# SCH_SrProj_v1_5.net
KiCad netlist of a schematic drawn in EasyEDA
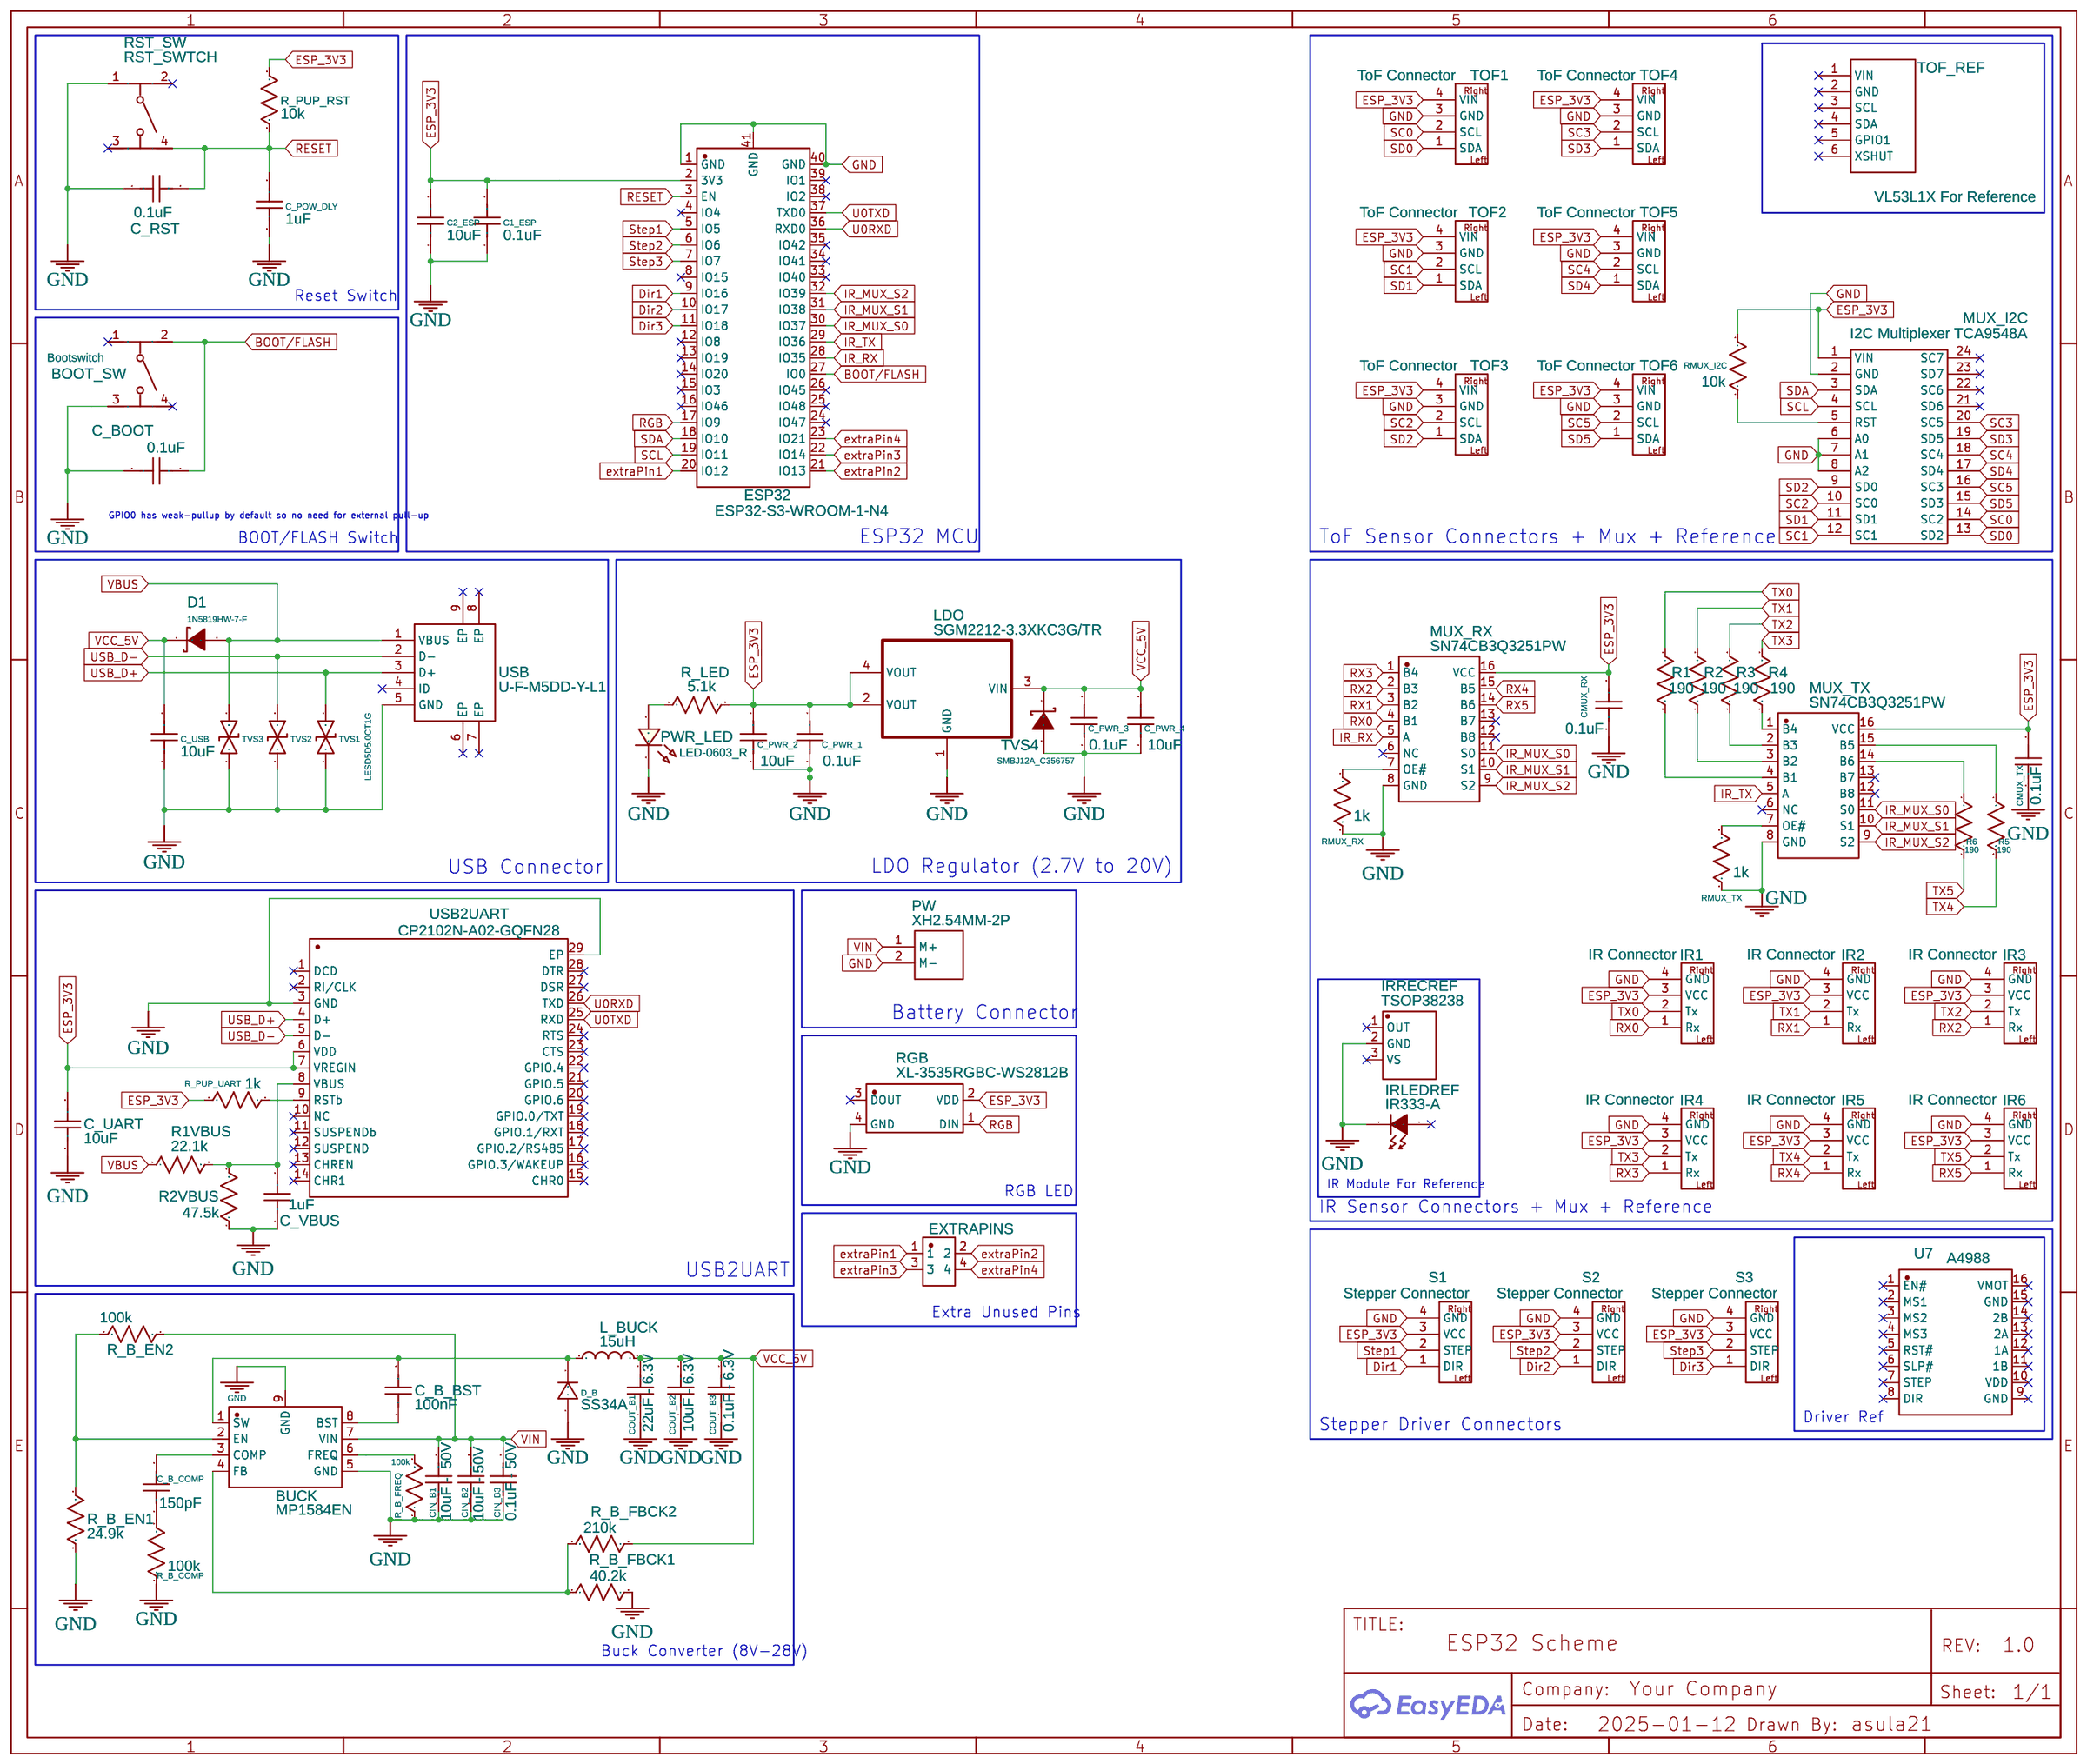
[diagram p0: schematic sheet]

(export (version "E")
  (design (tool "Eeschema 10.0.6"))
  (components
    (comp (ref "BOOT_SW")
      (value "Bootswitch")
      (fields
        (field (name "Manufacturer Part") "Switch,6*6*6Plastic head,260G, 0.25mm,Straight line")
        (field (name "Manufacturer") "BBJ")
      )
      (libsource (lib "") (part "Button-6x6x6mm_1"))
    )
    (comp (ref "BUCK") (value "MP1584EN") (libsource (lib "") (part "MP1584EN")))
    (comp (ref "C1_ESP") (value "0.1uF") (libsource (lib "") (part "C_0603_US_11")))
    (comp (ref "C2_ESP") (value "10uF") (libsource (lib "") (part "C_0603_US_8")))
    (comp (ref "CIN_B1") (value "10uF -  50V") (libsource (lib "") (part "C_0603_US_5")))
    (comp (ref "CIN_B2") (value "10uF - 50V") (libsource (lib "") (part "C_0603_US_5")))
    (comp (ref "CIN_B3") (value "0.1uF - 50V") (libsource (lib "") (part "C_0603_US_5")))
    (comp (ref "CMUX_RX") (value "0.1uF") (libsource (lib "") (part "C_0603_US_14")))
    (comp (ref "CMUX_TX") (value "0.1uF") (libsource (lib "") (part "C_0603_US_9")))
    (comp (ref "COUT_B1") (value "22uF - 6.3V") (libsource (lib "") (part "C_0603_US")))
    (comp (ref "COUT_B2") (value "10uF - 6.3V") (libsource (lib "") (part "C_0603_US")))
    (comp (ref "COUT_B3") (value "0.1uF - 6.3V") (libsource (lib "") (part "C_0603_US")))
    (comp (ref "C_BOOT") (value "0.1uF") (libsource (lib "") (part "C_0603_US_6")))
    (comp (ref "C_B_BST") (value "100nF") (libsource (lib "") (part "C_0603_US_4")))
    (comp (ref "C_B_COMP") (value "150pF") (libsource (lib "") (part "C_0603_US_13")))
    (comp (ref "C_POW_DLY") (value "1uF") (libsource (lib "") (part "C_0603_US_2")))
    (comp (ref "C_PWR_1") (value "0.1uF") (libsource (lib "") (part "C_0603_US_3")))
    (comp (ref "C_PWR_2") (value "10uF") (libsource (lib "") (part "C_0603_US_3")))
    (comp (ref "C_PWR_3") (value "0.1uF") (libsource (lib "") (part "C_0603_US_3")))
    (comp (ref "C_PWR_4") (value "10uF") (libsource (lib "") (part "C_0603_US_3")))
    (comp (ref "C_RST") (value "0.1uF") (libsource (lib "") (part "C_0603_US_12")))
    (comp (ref "C_UART") (value "10uF") (libsource (lib "") (part "C_0603_US_10")))
    (comp (ref "C_USB") (value "10uF") (libsource (lib "") (part "C_0603_US_1")))
    (comp (ref "C_VBUS") (value "1uF") (libsource (lib "") (part "C_0603_US_7")))
    (comp (ref "D1")
      (value "1N5819HW-7-F")
      (fields (field (name "Manufacturer") "DIODES(美台)"))
      (libsource (lib "") (part "1N5819HW-7-F"))
    )
    (comp (ref "D_B")
      (value "SS34A")
      (fields (field (name "Manufacturer") "YANGJIE(扬杰)"))
      (libsource (lib "") (part "SS34A"))
    )
    (comp (ref "ESP32")
      (value "ESP32-S3-WROOM-1-N4")
      (fields (field (name "Manufacturer") "ESPRESSIF(乐鑫)"))
      (libsource (lib "") (part "ESP32-S3-WROOM-1-N4"))
    )
    (comp (ref "EXTRAPINS")
      (value "排母/2.54MM2X2直排母袋装环保")
      (fields
        (field (name "Manufacturer Part") "排母/2.54mm2x2直排母袋装环保")
        (field (name "Manufacturer") "BOOMELE(博穆精密)")
      )
      (libsource (lib "") (part "排母/2.54MM2X2直排母袋装环保"))
    )
    (comp (ref "IR1") (value "IR Connector") (libsource (lib "") (part "MY XH2.54MM.4P_2")))
    (comp (ref "IR2") (value "IR Connector") (libsource (lib "") (part "MY XH2.54MM.4P_2")))
    (comp (ref "IR3") (value "IR Connector") (libsource (lib "") (part "MY XH2.54MM.4P_2")))
    (comp (ref "IR4") (value "IR Connector") (libsource (lib "") (part "MY XH2.54MM.4P_2")))
    (comp (ref "IR5") (value "IR Connector") (libsource (lib "") (part "MY XH2.54MM.4P_2")))
    (comp (ref "IR6") (value "IR Connector") (libsource (lib "") (part "MY XH2.54MM.4P_2")))
    (comp (ref "IRLEDREF")
      (value "IR333-A")
      (fields (field (name "Manufacturer") "EVERLIGHT(亿光)"))
      (libsource (lib "") (part "IR333-A"))
    )
    (comp (ref "IRRECREF")
      (value "TSOP38238")
      (fields (field (name "Manufacturer") "VISHAY(威世)"))
      (libsource (lib "") (part "TSOP38238"))
    )
    (comp (ref "LDO") (value "SGM2212-3.3XKC3G/TR") (libsource (lib "") (part "SGM2212-3.3XKC3G/TR")))
    (comp (ref "L_BUCK")
      (value "15uH")
      (fields (field (name "Manufacturer Part") "CYH127-4.7UH") (field (name "Manufacturer") "SHOU HAN(首韩)"))
      (libsource (lib "") (part "CYH127-4.7UH"))
    )
    (comp (ref "MUX_I2C")
      (value "I2C Multiplexer TCA9548A")
      (fields (field (name "Manufacturer Part") "IDSN-TCA9548A") (field (name "Manufacturer") "IDSN"))
      (libsource (lib "") (part "TCA9548A I2C MULTIPLEXER 8 CHANEL"))
    )
    (comp (ref "MUX_RX")
      (value "SN74CB3Q3251PW")
      (fields (field (name "Manufacturer") "TI(德州仪器)"))
      (libsource (lib "") (part "SN74CB3Q3251PW"))
    )
    (comp (ref "MUX_TX")
      (value "SN74CB3Q3251PW")
      (fields (field (name "Manufacturer") "TI(德州仪器)"))
      (libsource (lib "") (part "SN74CB3Q3251PW_1"))
    )
    (comp (ref "PW")
      (value "XH2.54MM-2P")
      (fields (field (name "Manufacturer Part") "Header P2 PH2.0 TUANLE"))
      (libsource (lib "") (part "PH2.0-2P"))
    )
    (comp (ref "PWR_LED")
      (value "LED-0603_R")
      (fields
        (field (name "Manufacturer Part") "19-217/R6C-AL1M2VY/3T")
        (field (name "Manufacturer") "EVERLIGHT(台湾亿光)")
      )
      (libsource (lib "") (part "LED-0603_R"))
    )
    (comp (ref "R1") (value "190") (libsource (lib "") (part "R_0805_US_1")))
    (comp (ref "R1VBUS") (value "22.1k") (libsource (lib "") (part "R_0603_US_3")))
    (comp (ref "R2") (value "190") (libsource (lib "") (part "R_0805_US")))
    (comp (ref "R2VBUS") (value "47.5k") (libsource (lib "") (part "R_0603_US_1")))
    (comp (ref "R3") (value "190") (libsource (lib "") (part "R_0805_US")))
    (comp (ref "R4") (value "190") (libsource (lib "") (part "R_0805_US")))
    (comp (ref "R5") (value "190") (libsource (lib "") (part "R_0805_US_1")))
    (comp (ref "R6") (value "190") (libsource (lib "") (part "R_0805_US")))
    (comp (ref "RGB")
      (value "XL-3535RGBC-WS2812B")
      (fields (field (name "Manufacturer") "XINGLIGHT(成兴光)"))
      (libsource (lib "") (part "XL-3535RGBC-WS2812B"))
    )
    (comp (ref "RMUX_I2C") (value "10k") (libsource (lib "") (part "R_0603_US_4")))
    (comp (ref "RMUX_RX") (value "1k") (libsource (lib "") (part "R_0603_US_11")))
    (comp (ref "RMUX_TX") (value "1k") (libsource (lib "") (part "R_0603_US_13")))
    (comp (ref "RST_SW")
      (value "RST_SWTCH")
      (fields
        (field (name "Manufacturer Part") "Switch,6*6*6Plastic head,260G, 0.25mm,Straight line")
        (field (name "Manufacturer") "BBJ")
      )
      (libsource (lib "") (part "Button-6x6x6mm"))
    )
    (comp (ref "R_B_COMP") (value "100k") (libsource (lib "") (part "R_0603_US_6")))
    (comp (ref "R_B_EN1") (value "24.9k") (libsource (lib "") (part "R_0603_US")))
    (comp (ref "R_B_EN2") (value "100k") (libsource (lib "") (part "R_0603_US_7")))
    (comp (ref "R_B_FBCK1") (value "40.2k") (libsource (lib "") (part "R_0603_US_10")))
    (comp (ref "R_B_FBCK2") (value "210k") (libsource (lib "") (part "R_0603_US_12")))
    (comp (ref "R_B_FREQ") (value "100k") (libsource (lib "") (part "R_0603_US_9")))
    (comp (ref "R_LED") (value "5.1k") (libsource (lib "") (part "R_0603_US_5")))
    (comp (ref "R_PUP_RST") (value "10k") (libsource (lib "") (part "R_0603_US_2")))
    (comp (ref "R_PUP_UART") (value "1k") (libsource (lib "") (part "R_0603_US_8")))
    (comp (ref "S1") (value "Stepper Connector") (libsource (lib "") (part "MY XH2.54MM.4P")))
    (comp (ref "S2") (value "Stepper Connector") (libsource (lib "") (part "MY XH2.54MM.4P")))
    (comp (ref "S3") (value "Stepper Connector") (libsource (lib "") (part "MY XH2.54MM.4P")))
    (comp (ref "TOF1") (value "ToF Connector") (libsource (lib "") (part "MY XH2.54MM.4P_1")))
    (comp (ref "TOF2") (value "ToF Connector") (libsource (lib "") (part "MY XH2.54MM.4P_1")))
    (comp (ref "TOF3") (value "ToF Connector") (libsource (lib "") (part "MY XH2.54MM.4P_1")))
    (comp (ref "TOF4") (value "ToF Connector") (libsource (lib "") (part "MY XH2.54MM.4P_1")))
    (comp (ref "TOF5") (value "ToF Connector") (libsource (lib "") (part "MY XH2.54MM.4P_1")))
    (comp (ref "TOF6") (value "ToF Connector") (libsource (lib "") (part "MY XH2.54MM.4P_1")))
    (comp (ref "TOF_REF")
      (value "VL53L1X For Reference")
      (fields (field (name "Manufacturer Part") "VL53L0X Time-of-Flight Distance Sensor VL53L0X"))
      (libsource (lib "") (part "VL53L1X_BREAKOUT"))
    )
    (comp (ref "TVS1")
      (value "LESD5D5.0CT1G")
      (fields (field (name "Manufacturer") "LRC(乐山无线电)"))
      (libsource (lib "") (part "LESD5D5.0CT1G"))
    )
    (comp (ref "TVS2")
      (value "LESD5D5.0CT1G")
      (fields (field (name "Manufacturer") "LRC(乐山无线电)"))
      (libsource (lib "") (part "LESD5D5.0CT1G"))
    )
    (comp (ref "TVS3")
      (value "LESD5D5.0CT1G")
      (fields (field (name "Manufacturer") "LRC(乐山无线电)"))
      (libsource (lib "") (part "LESD5D5.0CT1G"))
    )
    (comp (ref "TVS4")
      (value "SMBJ12A_C356757")
      (fields (field (name "Manufacturer Part") "SMBJ12A") (field (name "Manufacturer") "JJW(捷捷微)"))
      (libsource (lib "") (part "SMBJ12A_C356757"))
    )
    (comp (ref "U7") (value "A4988") (libsource (lib "") (part "A4988")))
    (comp (ref "USB")
      (value "U-F-M5DD-Y-L1")
      (fields (field (name "Manufacturer") "韩国韩荣"))
      (libsource (lib "") (part "U-F-M5DD-Y-L1"))
    )
    (comp (ref "USB2UART")
      (value "CP2102N-A02-GQFN28")
      (fields (field (name "Manufacturer") "SKYWORKS/SILICON LABS(芯科)"))
      (libsource (lib "") (part "CP2102N-A02-GQFN28"))
    )
  )
  (nets
    (net (code "1") (name "BOOT{slash}FLASH") (class "Default")
      (node (ref "BOOT_SW") (pin "2") (pinfunction "2_2") (pintype "unspecified"))
      (node (ref "C_BOOT") (pin "2") (pinfunction "2_2") (pintype "unspecified"))
      (node (ref "ESP32") (pin "27") (pinfunction "IO0_27") (pintype "unspecified"))
    )
    (net (code "2") (name "Dir1") (class "Default")
      (node (ref "ESP32") (pin "9") (pinfunction "IO16_9") (pintype "unspecified"))
      (node (ref "S1") (pin "1") (pinfunction "DIR_1") (pintype "unspecified"))
    )
    (net (code "3") (name "Dir2") (class "Default")
      (node (ref "ESP32") (pin "10") (pinfunction "IO17_10") (pintype "unspecified"))
      (node (ref "S2") (pin "1") (pinfunction "DIR_1") (pintype "unspecified"))
    )
    (net (code "4") (name "Dir3") (class "Default")
      (node (ref "ESP32") (pin "11") (pinfunction "IO18_11") (pintype "unspecified"))
      (node (ref "S3") (pin "1") (pinfunction "DIR_1") (pintype "unspecified"))
    )
    (net (code "5") (name "ESP_3V3") (class "Default")
      (node (ref "C1_ESP") (pin "2") (pinfunction "2_2") (pintype "unspecified"))
      (node (ref "C2_ESP") (pin "2") (pinfunction "2_2") (pintype "unspecified"))
      (node (ref "CMUX_RX") (pin "2") (pinfunction "2_2") (pintype "unspecified"))
      (node (ref "CMUX_TX") (pin "2") (pinfunction "2_2") (pintype "unspecified"))
      (node (ref "C_PWR_1") (pin "2") (pinfunction "2_2") (pintype "unspecified"))
      (node (ref "C_PWR_2") (pin "2") (pinfunction "2_2") (pintype "unspecified"))
      (node (ref "C_UART") (pin "2") (pinfunction "2_2") (pintype "unspecified"))
      (node (ref "ESP32") (pin "2") (pinfunction "3V3_2") (pintype "unspecified"))
      (node (ref "IR1") (pin "3") (pinfunction "VCC_3") (pintype "unspecified"))
      (node (ref "IR2") (pin "3") (pinfunction "VCC_3") (pintype "unspecified"))
      (node (ref "IR3") (pin "3") (pinfunction "VCC_3") (pintype "unspecified"))
      (node (ref "IR4") (pin "3") (pinfunction "VCC_3") (pintype "unspecified"))
      (node (ref "IR5") (pin "3") (pinfunction "VCC_3") (pintype "unspecified"))
      (node (ref "IR6") (pin "3") (pinfunction "VCC_3") (pintype "unspecified"))
      (node (ref "LDO") (pin "2") (pinfunction "VOUT_2") (pintype "unspecified"))
      (node (ref "LDO") (pin "4") (pinfunction "VOUT_4") (pintype "unspecified"))
      (node (ref "MUX_I2C") (pin "1") (pinfunction "VIN_1") (pintype "unspecified"))
      (node (ref "MUX_RX") (pin "16") (pinfunction "VCC_16") (pintype "unspecified"))
      (node (ref "MUX_TX") (pin "16") (pinfunction "VCC_16") (pintype "unspecified"))
      (node (ref "RGB") (pin "2") (pinfunction "VDD_2") (pintype "unspecified"))
      (node (ref "RMUX_I2C") (pin "2") (pinfunction "2_2") (pintype "unspecified"))
      (node (ref "R_LED") (pin "2") (pinfunction "2_2") (pintype "unspecified"))
      (node (ref "R_PUP_RST") (pin "2") (pinfunction "2_2") (pintype "unspecified"))
      (node (ref "R_PUP_UART") (pin "2") (pinfunction "2_2") (pintype "unspecified"))
      (node (ref "S1") (pin "3") (pinfunction "VCC_3") (pintype "unspecified"))
      (node (ref "S2") (pin "3") (pinfunction "VCC_3") (pintype "unspecified"))
      (node (ref "S3") (pin "3") (pinfunction "VCC_3") (pintype "unspecified"))
      (node (ref "TOF1") (pin "4") (pinfunction "VIN_4") (pintype "unspecified"))
      (node (ref "TOF2") (pin "4") (pinfunction "VIN_4") (pintype "unspecified"))
      (node (ref "TOF3") (pin "4") (pinfunction "VIN_4") (pintype "unspecified"))
      (node (ref "TOF4") (pin "4") (pinfunction "VIN_4") (pintype "unspecified"))
      (node (ref "TOF5") (pin "4") (pinfunction "VIN_4") (pintype "unspecified"))
      (node (ref "TOF6") (pin "4") (pinfunction "VIN_4") (pintype "unspecified"))
      (node (ref "USB2UART") (pin "6") (pinfunction "VDD_6") (pintype "unspecified"))
      (node (ref "USB2UART") (pin "7") (pinfunction "VREGIN_7") (pintype "unspecified"))
    )
    (net (code "6") (name "GND") (class "Default")
      (node (ref "BOOT_SW") (pin "3") (pinfunction "3_3") (pintype "unspecified"))
      (node (ref "BUCK") (pin "5") (pinfunction "GND_5") (pintype "unspecified"))
      (node (ref "BUCK") (pin "9") (pinfunction "GND_9") (pintype "unspecified"))
      (node (ref "C1_ESP") (pin "1") (pinfunction "1_1") (pintype "unspecified"))
      (node (ref "C2_ESP") (pin "1") (pinfunction "1_1") (pintype "unspecified"))
      (node (ref "CIN_B1") (pin "1") (pinfunction "1_1") (pintype "unspecified"))
      (node (ref "CIN_B2") (pin "1") (pinfunction "1_1") (pintype "unspecified"))
      (node (ref "CIN_B3") (pin "1") (pinfunction "1_1") (pintype "unspecified"))
      (node (ref "CMUX_RX") (pin "1") (pinfunction "1_1") (pintype "unspecified"))
      (node (ref "CMUX_TX") (pin "1") (pinfunction "1_1") (pintype "unspecified"))
      (node (ref "COUT_B1") (pin "1") (pinfunction "1_1") (pintype "unspecified"))
      (node (ref "COUT_B2") (pin "1") (pinfunction "1_1") (pintype "unspecified"))
      (node (ref "COUT_B3") (pin "1") (pinfunction "1_1") (pintype "unspecified"))
      (node (ref "C_BOOT") (pin "1") (pinfunction "1_1") (pintype "unspecified"))
      (node (ref "C_POW_DLY") (pin "1") (pinfunction "1_1") (pintype "unspecified"))
      (node (ref "C_PWR_1") (pin "1") (pinfunction "1_1") (pintype "unspecified"))
      (node (ref "C_PWR_2") (pin "1") (pinfunction "1_1") (pintype "unspecified"))
      (node (ref "C_PWR_3") (pin "1") (pinfunction "1_1") (pintype "unspecified"))
      (node (ref "C_PWR_4") (pin "1") (pinfunction "1_1") (pintype "unspecified"))
      (node (ref "C_RST") (pin "1") (pinfunction "1_1") (pintype "unspecified"))
      (node (ref "C_UART") (pin "1") (pinfunction "1_1") (pintype "unspecified"))
      (node (ref "C_USB") (pin "1") (pinfunction "1_1") (pintype "unspecified"))
      (node (ref "C_VBUS") (pin "2") (pinfunction "2_2") (pintype "unspecified"))
      (node (ref "D_B") (pin "2") (pinfunction "A_2") (pintype "unspecified"))
      (node (ref "ESP32") (pin "1") (pinfunction "GND_1") (pintype "unspecified"))
      (node (ref "ESP32") (pin "40") (pinfunction "GND_40") (pintype "unspecified"))
      (node (ref "ESP32") (pin "41") (pinfunction "GND_41") (pintype "unspecified"))
      (node (ref "IR1") (pin "4") (pinfunction "GND_4") (pintype "unspecified"))
      (node (ref "IR2") (pin "4") (pinfunction "GND_4") (pintype "unspecified"))
      (node (ref "IR3") (pin "4") (pinfunction "GND_4") (pintype "unspecified"))
      (node (ref "IR4") (pin "4") (pinfunction "GND_4") (pintype "unspecified"))
      (node (ref "IR5") (pin "4") (pinfunction "GND_4") (pintype "unspecified"))
      (node (ref "IR6") (pin "4") (pinfunction "GND_4") (pintype "unspecified"))
      (node (ref "IRLEDREF") (pin "2") (pinfunction "C_2") (pintype "input"))
      (node (ref "IRRECREF") (pin "2") (pinfunction "GND_2") (pintype "unspecified"))
      (node (ref "LDO") (pin "1") (pinfunction "GND_1") (pintype "unspecified"))
      (node (ref "MUX_I2C") (pin "2") (pinfunction "GND_2") (pintype "unspecified"))
      (node (ref "MUX_I2C") (pin "6") (pinfunction "A0_6") (pintype "unspecified"))
      (node (ref "MUX_I2C") (pin "7") (pinfunction "A1_7") (pintype "unspecified"))
      (node (ref "MUX_I2C") (pin "8") (pinfunction "A2_8") (pintype "unspecified"))
      (node (ref "MUX_RX") (pin "8") (pinfunction "GND_8") (pintype "unspecified"))
      (node (ref "MUX_TX") (pin "8") (pinfunction "GND_8") (pintype "unspecified"))
      (node (ref "PW") (pin "2") (pinfunction "M-_2") (pintype "unspecified"))
      (node (ref "PWR_LED") (pin "2") (pinfunction "2_2") (pintype "unspecified"))
      (node (ref "R2VBUS") (pin "1") (pinfunction "1_1") (pintype "unspecified"))
      (node (ref "RGB") (pin "4") (pinfunction "GND_4") (pintype "unspecified"))
      (node (ref "RMUX_RX") (pin "1") (pinfunction "1_1") (pintype "unspecified"))
      (node (ref "RMUX_TX") (pin "1") (pinfunction "1_1") (pintype "unspecified"))
      (node (ref "RST_SW") (pin "1") (pinfunction "1_1") (pintype "unspecified"))
      (node (ref "R_B_COMP") (pin "1") (pinfunction "1_1") (pintype "unspecified"))
      (node (ref "R_B_EN1") (pin "1") (pinfunction "1_1") (pintype "unspecified"))
      (node (ref "R_B_FBCK1") (pin "2") (pinfunction "2_2") (pintype "unspecified"))
      (node (ref "R_B_FREQ") (pin "1") (pinfunction "1_1") (pintype "unspecified"))
      (node (ref "S1") (pin "4") (pinfunction "GND_4") (pintype "unspecified"))
      (node (ref "S2") (pin "4") (pinfunction "GND_4") (pintype "unspecified"))
      (node (ref "S3") (pin "4") (pinfunction "GND_4") (pintype "unspecified"))
      (node (ref "TOF1") (pin "3") (pinfunction "GND_3") (pintype "unspecified"))
      (node (ref "TOF2") (pin "3") (pinfunction "GND_3") (pintype "unspecified"))
      (node (ref "TOF3") (pin "3") (pinfunction "GND_3") (pintype "unspecified"))
      (node (ref "TOF4") (pin "3") (pinfunction "GND_3") (pintype "unspecified"))
      (node (ref "TOF5") (pin "3") (pinfunction "GND_3") (pintype "unspecified"))
      (node (ref "TOF6") (pin "3") (pinfunction "GND_3") (pintype "unspecified"))
      (node (ref "TVS1") (pin "1") (pinfunction "1_1") (pintype "unspecified"))
      (node (ref "TVS2") (pin "1") (pinfunction "1_1") (pintype "unspecified"))
      (node (ref "TVS3") (pin "1") (pinfunction "1_1") (pintype "unspecified"))
      (node (ref "TVS4") (pin "2") (pinfunction "A_2") (pintype "unspecified"))
      (node (ref "USB") (pin "5") (pinfunction "GND_5") (pintype "unspecified"))
      (node (ref "USB2UART") (pin "29") (pinfunction "EP_29") (pintype "unspecified"))
      (node (ref "USB2UART") (pin "3") (pinfunction "GND_3") (pintype "unspecified"))
    )
    (net (code "7") (name "IR_MUX_S0") (class "Default")
      (node (ref "ESP32") (pin "30") (pinfunction "IO37_30") (pintype "unspecified"))
      (node (ref "MUX_RX") (pin "11") (pinfunction "S0_11") (pintype "unspecified"))
      (node (ref "MUX_TX") (pin "11") (pinfunction "S0_11") (pintype "unspecified"))
    )
    (net (code "8") (name "IR_MUX_S1") (class "Default")
      (node (ref "ESP32") (pin "31") (pinfunction "IO38_31") (pintype "unspecified"))
      (node (ref "MUX_RX") (pin "10") (pinfunction "S1_10") (pintype "unspecified"))
      (node (ref "MUX_TX") (pin "10") (pinfunction "S1_10") (pintype "unspecified"))
    )
    (net (code "9") (name "IR_MUX_S2") (class "Default")
      (node (ref "ESP32") (pin "32") (pinfunction "IO39_32") (pintype "unspecified"))
      (node (ref "MUX_RX") (pin "9") (pinfunction "S2_9") (pintype "unspecified"))
      (node (ref "MUX_TX") (pin "9") (pinfunction "S2_9") (pintype "unspecified"))
    )
    (net (code "10") (name "IR_RX") (class "Default")
      (node (ref "ESP32") (pin "28") (pinfunction "IO35_28") (pintype "unspecified"))
      (node (ref "MUX_RX") (pin "5") (pinfunction "A_5") (pintype "unspecified"))
    )
    (net (code "11") (name "IR_TX") (class "Default")
      (node (ref "ESP32") (pin "29") (pinfunction "IO36_29") (pintype "unspecified"))
      (node (ref "MUX_TX") (pin "5") (pinfunction "A_5") (pintype "unspecified"))
    )
    (net (code "12") (name "Net-(BUCK-BST)") (class "Default")
      (node (ref "BUCK") (pin "8") (pinfunction "BST_8") (pintype "unspecified"))
      (node (ref "C_B_BST") (pin "1") (pinfunction "1_1") (pintype "unspecified"))
    )
    (net (code "13") (name "Net-(BUCK-COMP)") (class "Default")
      (node (ref "BUCK") (pin "3") (pinfunction "COMP_3") (pintype "unspecified"))
      (node (ref "C_B_COMP") (pin "2") (pinfunction "2_2") (pintype "unspecified"))
    )
    (net (code "14") (name "Net-(BUCK-EN)") (class "Default")
      (node (ref "BUCK") (pin "2") (pinfunction "EN_2") (pintype "unspecified"))
      (node (ref "R_B_EN1") (pin "2") (pinfunction "2_2") (pintype "unspecified"))
      (node (ref "R_B_EN2") (pin "1") (pinfunction "1_1") (pintype "unspecified"))
    )
    (net (code "15") (name "Net-(BUCK-FB)") (class "Default")
      (node (ref "BUCK") (pin "4") (pinfunction "FB_4") (pintype "unspecified"))
      (node (ref "R_B_FBCK1") (pin "1") (pinfunction "1_1") (pintype "unspecified"))
      (node (ref "R_B_FBCK2") (pin "2") (pinfunction "2_2") (pintype "unspecified"))
    )
    (net (code "16") (name "Net-(BUCK-FREQ)") (class "Default")
      (node (ref "BUCK") (pin "6") (pinfunction "FREQ_6") (pintype "unspecified"))
      (node (ref "R_B_FREQ") (pin "2") (pinfunction "2_2") (pintype "unspecified"))
    )
    (net (code "17") (name "Net-(BUCK-SW)") (class "Default")
      (node (ref "BUCK") (pin "1") (pinfunction "SW_1") (pintype "unspecified"))
      (node (ref "C_B_BST") (pin "2") (pinfunction "2_2") (pintype "unspecified"))
      (node (ref "D_B") (pin "1") (pinfunction "C_1") (pintype "unspecified"))
      (node (ref "L_BUCK") (pin "1") (pinfunction "1_1") (pintype "unspecified"))
    )
    (net (code "18") (name "Net-(C_B_COMP-Pad1)") (class "Default")
      (node (ref "C_B_COMP") (pin "1") (pinfunction "1_1") (pintype "unspecified"))
      (node (ref "R_B_COMP") (pin "2") (pinfunction "2_2") (pintype "unspecified"))
    )
    (net (code "19") (name "Net-(MUX_I2C-RST)") (class "Default")
      (node (ref "MUX_I2C") (pin "5") (pinfunction "RST_5") (pintype "unspecified"))
      (node (ref "RMUX_I2C") (pin "1") (pinfunction "1_1") (pintype "unspecified"))
    )
    (net (code "20") (name "Net-(MUX_RX-OE#)") (class "Default")
      (node (ref "MUX_RX") (pin "7") (pinfunction "OE#_7") (pintype "unspecified"))
      (node (ref "RMUX_RX") (pin "2") (pinfunction "2_2") (pintype "unspecified"))
    )
    (net (code "21") (name "Net-(MUX_TX-B1)") (class "Default")
      (node (ref "MUX_TX") (pin "4") (pinfunction "B1_4") (pintype "unspecified"))
      (node (ref "R1") (pin "2") (pinfunction "2_2") (pintype "unspecified"))
    )
    (net (code "22") (name "Net-(MUX_TX-B2)") (class "Default")
      (node (ref "MUX_TX") (pin "3") (pinfunction "B2_3") (pintype "unspecified"))
      (node (ref "R2") (pin "1") (pinfunction "1_1") (pintype "unspecified"))
    )
    (net (code "23") (name "Net-(MUX_TX-B3)") (class "Default")
      (node (ref "MUX_TX") (pin "2") (pinfunction "B3_2") (pintype "unspecified"))
      (node (ref "R3") (pin "1") (pinfunction "1_1") (pintype "unspecified"))
    )
    (net (code "24") (name "Net-(MUX_TX-B4)") (class "Default")
      (node (ref "MUX_TX") (pin "1") (pinfunction "B4_1") (pintype "unspecified"))
      (node (ref "R4") (pin "1") (pinfunction "1_1") (pintype "unspecified"))
    )
    (net (code "25") (name "Net-(MUX_TX-B5)") (class "Default")
      (node (ref "MUX_TX") (pin "15") (pinfunction "B5_15") (pintype "unspecified"))
      (node (ref "R5") (pin "1") (pinfunction "1_1") (pintype "unspecified"))
    )
    (net (code "26") (name "Net-(MUX_TX-B6)") (class "Default")
      (node (ref "MUX_TX") (pin "14") (pinfunction "B6_14") (pintype "unspecified"))
      (node (ref "R6") (pin "2") (pinfunction "2_2") (pintype "unspecified"))
    )
    (net (code "27") (name "Net-(MUX_TX-OE#)") (class "Default")
      (node (ref "MUX_TX") (pin "7") (pinfunction "OE#_7") (pintype "unspecified"))
      (node (ref "RMUX_TX") (pin "2") (pinfunction "2_2") (pintype "unspecified"))
    )
    (net (code "28") (name "Net-(PWR_LED-Pad1)") (class "Default")
      (node (ref "PWR_LED") (pin "1") (pinfunction "1_1") (pintype "unspecified"))
      (node (ref "R_LED") (pin "1") (pinfunction "1_1") (pintype "unspecified"))
    )
    (net (code "29") (name "Net-(USB2UART-RSTb)") (class "Default")
      (node (ref "R_PUP_UART") (pin "1") (pinfunction "1_1") (pintype "unspecified"))
      (node (ref "USB2UART") (pin "9") (pinfunction "RSTb_9") (pintype "unspecified"))
    )
    (net (code "30") (name "Net-(USB2UART-VBUS)") (class "Default")
      (node (ref "C_VBUS") (pin "1") (pinfunction "1_1") (pintype "unspecified"))
      (node (ref "R1VBUS") (pin "2") (pinfunction "2_2") (pintype "unspecified"))
      (node (ref "R2VBUS") (pin "2") (pinfunction "2_2") (pintype "unspecified"))
      (node (ref "USB2UART") (pin "8") (pinfunction "VBUS_8") (pintype "unspecified"))
    )
    (net (code "31") (name "RESET") (class "Default")
      (node (ref "C_POW_DLY") (pin "2") (pinfunction "2_2") (pintype "unspecified"))
      (node (ref "C_RST") (pin "2") (pinfunction "2_2") (pintype "unspecified"))
      (node (ref "ESP32") (pin "3") (pinfunction "EN_3") (pintype "unspecified"))
      (node (ref "RST_SW") (pin "4") (pinfunction "4_4") (pintype "unspecified"))
      (node (ref "R_PUP_RST") (pin "1") (pinfunction "1_1") (pintype "unspecified"))
    )
    (net (code "32") (name "RGB") (class "Default")
      (node (ref "ESP32") (pin "17") (pinfunction "IO9_17") (pintype "unspecified"))
      (node (ref "RGB") (pin "1") (pinfunction "DIN_1") (pintype "unspecified"))
    )
    (net (code "33") (name "RX0") (class "Default")
      (node (ref "IR1") (pin "1") (pinfunction "Rx_1") (pintype "unspecified"))
      (node (ref "MUX_RX") (pin "4") (pinfunction "B1_4") (pintype "unspecified"))
    )
    (net (code "34") (name "RX1") (class "Default")
      (node (ref "IR2") (pin "1") (pinfunction "Rx_1") (pintype "unspecified"))
      (node (ref "MUX_RX") (pin "3") (pinfunction "B2_3") (pintype "unspecified"))
    )
    (net (code "35") (name "RX2") (class "Default")
      (node (ref "IR3") (pin "1") (pinfunction "Rx_1") (pintype "unspecified"))
      (node (ref "MUX_RX") (pin "2") (pinfunction "B3_2") (pintype "unspecified"))
    )
    (net (code "36") (name "RX3") (class "Default")
      (node (ref "IR4") (pin "1") (pinfunction "Rx_1") (pintype "unspecified"))
      (node (ref "MUX_RX") (pin "1") (pinfunction "B4_1") (pintype "unspecified"))
    )
    (net (code "37") (name "RX4") (class "Default")
      (node (ref "IR5") (pin "1") (pinfunction "Rx_1") (pintype "unspecified"))
      (node (ref "MUX_RX") (pin "15") (pinfunction "B5_15") (pintype "unspecified"))
    )
    (net (code "38") (name "RX5") (class "Default")
      (node (ref "IR6") (pin "1") (pinfunction "Rx_1") (pintype "unspecified"))
      (node (ref "MUX_RX") (pin "14") (pinfunction "B6_14") (pintype "unspecified"))
    )
    (net (code "39") (name "SC0") (class "Default")
      (node (ref "MUX_I2C") (pin "14") (pinfunction "SC2_14") (pintype "unspecified"))
      (node (ref "TOF1") (pin "2") (pinfunction "SCL_2") (pintype "unspecified"))
    )
    (net (code "40") (name "SC1") (class "Default")
      (node (ref "MUX_I2C") (pin "12") (pinfunction "SC1_12") (pintype "unspecified"))
      (node (ref "TOF2") (pin "2") (pinfunction "SCL_2") (pintype "unspecified"))
    )
    (net (code "41") (name "SC2") (class "Default")
      (node (ref "MUX_I2C") (pin "10") (pinfunction "SC0_10") (pintype "unspecified"))
      (node (ref "TOF3") (pin "2") (pinfunction "SCL_2") (pintype "unspecified"))
    )
    (net (code "42") (name "SC3") (class "Default")
      (node (ref "MUX_I2C") (pin "20") (pinfunction "SC5_20") (pintype "unspecified"))
      (node (ref "TOF4") (pin "2") (pinfunction "SCL_2") (pintype "unspecified"))
    )
    (net (code "43") (name "SC4") (class "Default")
      (node (ref "MUX_I2C") (pin "18") (pinfunction "SC4_18") (pintype "unspecified"))
      (node (ref "TOF5") (pin "2") (pinfunction "SCL_2") (pintype "unspecified"))
    )
    (net (code "44") (name "SC5") (class "Default")
      (node (ref "MUX_I2C") (pin "16") (pinfunction "SC3_16") (pintype "unspecified"))
      (node (ref "TOF6") (pin "2") (pinfunction "SCL_2") (pintype "unspecified"))
    )
    (net (code "45") (name "SCL") (class "Default")
      (node (ref "ESP32") (pin "19") (pinfunction "IO11_19") (pintype "unspecified"))
      (node (ref "MUX_I2C") (pin "4") (pinfunction "SCL_4") (pintype "unspecified"))
    )
    (net (code "46") (name "SD0") (class "Default")
      (node (ref "MUX_I2C") (pin "13") (pinfunction "SD2_13") (pintype "unspecified"))
      (node (ref "TOF1") (pin "1") (pinfunction "SDA_1") (pintype "unspecified"))
    )
    (net (code "47") (name "SD1") (class "Default")
      (node (ref "MUX_I2C") (pin "11") (pinfunction "SD1_11") (pintype "unspecified"))
      (node (ref "TOF2") (pin "1") (pinfunction "SDA_1") (pintype "unspecified"))
    )
    (net (code "48") (name "SD2") (class "Default")
      (node (ref "MUX_I2C") (pin "9") (pinfunction "SD0_9") (pintype "unspecified"))
      (node (ref "TOF3") (pin "1") (pinfunction "SDA_1") (pintype "unspecified"))
    )
    (net (code "49") (name "SD3") (class "Default")
      (node (ref "MUX_I2C") (pin "19") (pinfunction "SD5_19") (pintype "unspecified"))
      (node (ref "TOF4") (pin "1") (pinfunction "SDA_1") (pintype "unspecified"))
    )
    (net (code "50") (name "SD4") (class "Default")
      (node (ref "MUX_I2C") (pin "17") (pinfunction "SD4_17") (pintype "unspecified"))
      (node (ref "TOF5") (pin "1") (pinfunction "SDA_1") (pintype "unspecified"))
    )
    (net (code "51") (name "SD5") (class "Default")
      (node (ref "MUX_I2C") (pin "15") (pinfunction "SD3_15") (pintype "unspecified"))
      (node (ref "TOF6") (pin "1") (pinfunction "SDA_1") (pintype "unspecified"))
    )
    (net (code "52") (name "SDA") (class "Default")
      (node (ref "ESP32") (pin "18") (pinfunction "IO10_18") (pintype "unspecified"))
      (node (ref "MUX_I2C") (pin "3") (pinfunction "SDA_3") (pintype "unspecified"))
    )
    (net (code "53") (name "Step1") (class "Default")
      (node (ref "ESP32") (pin "5") (pinfunction "IO5_5") (pintype "unspecified"))
      (node (ref "S1") (pin "2") (pinfunction "STEP_2") (pintype "unspecified"))
    )
    (net (code "54") (name "Step2") (class "Default")
      (node (ref "ESP32") (pin "6") (pinfunction "IO6_6") (pintype "unspecified"))
      (node (ref "S2") (pin "2") (pinfunction "STEP_2") (pintype "unspecified"))
    )
    (net (code "55") (name "Step3") (class "Default")
      (node (ref "ESP32") (pin "7") (pinfunction "IO7_7") (pintype "unspecified"))
      (node (ref "S3") (pin "2") (pinfunction "STEP_2") (pintype "unspecified"))
    )
    (net (code "56") (name "TX0") (class "Default")
      (node (ref "IR1") (pin "2") (pinfunction "Tx_2") (pintype "unspecified"))
      (node (ref "R1") (pin "1") (pinfunction "1_1") (pintype "unspecified"))
    )
    (net (code "57") (name "TX1") (class "Default")
      (node (ref "IR2") (pin "2") (pinfunction "Tx_2") (pintype "unspecified"))
      (node (ref "R2") (pin "2") (pinfunction "2_2") (pintype "unspecified"))
    )
    (net (code "58") (name "TX2") (class "Default")
      (node (ref "IR3") (pin "2") (pinfunction "Tx_2") (pintype "unspecified"))
      (node (ref "R3") (pin "2") (pinfunction "2_2") (pintype "unspecified"))
    )
    (net (code "59") (name "TX3") (class "Default")
      (node (ref "IR4") (pin "2") (pinfunction "Tx_2") (pintype "unspecified"))
      (node (ref "R4") (pin "2") (pinfunction "2_2") (pintype "unspecified"))
    )
    (net (code "60") (name "TX4") (class "Default")
      (node (ref "IR5") (pin "2") (pinfunction "Tx_2") (pintype "unspecified"))
      (node (ref "R5") (pin "2") (pinfunction "2_2") (pintype "unspecified"))
    )
    (net (code "61") (name "TX5") (class "Default")
      (node (ref "IR6") (pin "2") (pinfunction "Tx_2") (pintype "unspecified"))
      (node (ref "R6") (pin "1") (pinfunction "1_1") (pintype "unspecified"))
    )
    (net (code "62") (name "U0RXD") (class "Default")
      (node (ref "ESP32") (pin "36") (pinfunction "RXD0_36") (pintype "unspecified"))
      (node (ref "USB2UART") (pin "26") (pinfunction "TXD_26") (pintype "unspecified"))
    )
    (net (code "63") (name "U0TXD") (class "Default")
      (node (ref "ESP32") (pin "37") (pinfunction "TXD0_37") (pintype "unspecified"))
      (node (ref "USB2UART") (pin "25") (pinfunction "RXD_25") (pintype "unspecified"))
    )
    (net (code "64") (name "USB_D+") (class "Default")
      (node (ref "TVS1") (pin "2") (pinfunction "2_2") (pintype "unspecified"))
      (node (ref "USB") (pin "3") (pinfunction "D+_3") (pintype "unspecified"))
      (node (ref "USB2UART") (pin "4") (pinfunction "D+_4") (pintype "unspecified"))
    )
    (net (code "65") (name "USB_D-") (class "Default")
      (node (ref "TVS2") (pin "2") (pinfunction "2_2") (pintype "unspecified"))
      (node (ref "USB") (pin "2") (pinfunction "D-_2") (pintype "unspecified"))
      (node (ref "USB2UART") (pin "5") (pinfunction "D-_5") (pintype "unspecified"))
    )
    (net (code "66") (name "VBUS") (class "Default")
      (node (ref "D1") (pin "2") (pinfunction "A_2") (pintype "unspecified"))
      (node (ref "R1VBUS") (pin "1") (pinfunction "1_1") (pintype "unspecified"))
      (node (ref "TVS3") (pin "2") (pinfunction "2_2") (pintype "unspecified"))
      (node (ref "USB") (pin "1") (pinfunction "VBUS_1") (pintype "unspecified"))
    )
    (net (code "67") (name "VCC_5V") (class "Default")
      (node (ref "COUT_B1") (pin "2") (pinfunction "2_2") (pintype "unspecified"))
      (node (ref "COUT_B2") (pin "2") (pinfunction "2_2") (pintype "unspecified"))
      (node (ref "COUT_B3") (pin "2") (pinfunction "2_2") (pintype "unspecified"))
      (node (ref "C_PWR_3") (pin "2") (pinfunction "2_2") (pintype "unspecified"))
      (node (ref "C_PWR_4") (pin "2") (pinfunction "2_2") (pintype "unspecified"))
      (node (ref "C_USB") (pin "2") (pinfunction "2_2") (pintype "unspecified"))
      (node (ref "D1") (pin "1") (pinfunction "K_1") (pintype "unspecified"))
      (node (ref "LDO") (pin "3") (pinfunction "VIN_3") (pintype "unspecified"))
      (node (ref "L_BUCK") (pin "2") (pinfunction "2_2") (pintype "unspecified"))
      (node (ref "R_B_FBCK2") (pin "1") (pinfunction "1_1") (pintype "unspecified"))
      (node (ref "TVS4") (pin "1") (pinfunction "K_1") (pintype "unspecified"))
    )
    (net (code "68") (name "VIN") (class "Default")
      (node (ref "BUCK") (pin "7") (pinfunction "VIN_7") (pintype "unspecified"))
      (node (ref "CIN_B1") (pin "2") (pinfunction "2_2") (pintype "unspecified"))
      (node (ref "CIN_B2") (pin "2") (pinfunction "2_2") (pintype "unspecified"))
      (node (ref "CIN_B3") (pin "2") (pinfunction "2_2") (pintype "unspecified"))
      (node (ref "PW") (pin "1") (pinfunction "M+_1") (pintype "unspecified"))
      (node (ref "R_B_EN2") (pin "2") (pinfunction "2_2") (pintype "unspecified"))
    )
    (net (code "69") (name "extraPin1") (class "Default")
      (node (ref "ESP32") (pin "20") (pinfunction "IO12_20") (pintype "unspecified"))
      (node (ref "EXTRAPINS") (pin "1") (pinfunction "1_1") (pintype "unspecified"))
    )
    (net (code "70") (name "extraPin2") (class "Default")
      (node (ref "ESP32") (pin "21") (pinfunction "IO13_21") (pintype "unspecified"))
      (node (ref "EXTRAPINS") (pin "2") (pinfunction "2_2") (pintype "unspecified"))
    )
    (net (code "71") (name "extraPin3") (class "Default")
      (node (ref "ESP32") (pin "22") (pinfunction "IO14_22") (pintype "unspecified"))
      (node (ref "EXTRAPINS") (pin "3") (pinfunction "3_3") (pintype "unspecified"))
    )
    (net (code "72") (name "extraPin4") (class "Default")
      (node (ref "ESP32") (pin "23") (pinfunction "IO21_23") (pintype "unspecified"))
      (node (ref "EXTRAPINS") (pin "4") (pinfunction "4_4") (pintype "unspecified"))
    )
    (net (code "73") (name "unconnected-(BOOT_SW-Pad1)") (class "Default")
      (node (ref "BOOT_SW") (pin "1") (pinfunction "1_1") (pintype "unspecified+no_connect"))
    )
    (net (code "74") (name "unconnected-(BOOT_SW-Pad4)") (class "Default")
      (node (ref "BOOT_SW") (pin "4") (pinfunction "4_4") (pintype "unspecified+no_connect"))
    )
    (net (code "75") (name "unconnected-(ESP32-IO1-Pad39)") (class "Default")
      (node (ref "ESP32") (pin "39") (pinfunction "IO1_39") (pintype "unspecified+no_connect"))
    )
    (net (code "76") (name "unconnected-(ESP32-IO2-Pad38)") (class "Default")
      (node (ref "ESP32") (pin "38") (pinfunction "IO2_38") (pintype "unspecified+no_connect"))
    )
    (net (code "77") (name "unconnected-(ESP32-IO3-Pad15)") (class "Default")
      (node (ref "ESP32") (pin "15") (pinfunction "IO3_15") (pintype "unspecified+no_connect"))
    )
    (net (code "78") (name "unconnected-(ESP32-IO4-Pad4)") (class "Default")
      (node (ref "ESP32") (pin "4") (pinfunction "IO4_4") (pintype "unspecified+no_connect"))
    )
    (net (code "79") (name "unconnected-(ESP32-IO8-Pad12)") (class "Default")
      (node (ref "ESP32") (pin "12") (pinfunction "IO8_12") (pintype "unspecified+no_connect"))
    )
    (net (code "80") (name "unconnected-(ESP32-IO15-Pad8)") (class "Default")
      (node (ref "ESP32") (pin "8") (pinfunction "IO15_8") (pintype "unspecified+no_connect"))
    )
    (net (code "81") (name "unconnected-(ESP32-IO19-Pad13)") (class "Default")
      (node (ref "ESP32") (pin "13") (pinfunction "IO19_13") (pintype "unspecified+no_connect"))
    )
    (net (code "82") (name "unconnected-(ESP32-IO20-Pad14)") (class "Default")
      (node (ref "ESP32") (pin "14") (pinfunction "IO20_14") (pintype "unspecified+no_connect"))
    )
    (net (code "83") (name "unconnected-(ESP32-IO40-Pad33)") (class "Default")
      (node (ref "ESP32") (pin "33") (pinfunction "IO40_33") (pintype "unspecified+no_connect"))
    )
    (net (code "84") (name "unconnected-(ESP32-IO41-Pad34)") (class "Default")
      (node (ref "ESP32") (pin "34") (pinfunction "IO41_34") (pintype "unspecified+no_connect"))
    )
    (net (code "85") (name "unconnected-(ESP32-IO42-Pad35)") (class "Default")
      (node (ref "ESP32") (pin "35") (pinfunction "IO42_35") (pintype "unspecified+no_connect"))
    )
    (net (code "86") (name "unconnected-(ESP32-IO45-Pad26)") (class "Default")
      (node (ref "ESP32") (pin "26") (pinfunction "IO45_26") (pintype "unspecified+no_connect"))
    )
    (net (code "87") (name "unconnected-(ESP32-IO46-Pad16)") (class "Default")
      (node (ref "ESP32") (pin "16") (pinfunction "IO46_16") (pintype "unspecified+no_connect"))
    )
    (net (code "88") (name "unconnected-(ESP32-IO47-Pad24)") (class "Default")
      (node (ref "ESP32") (pin "24") (pinfunction "IO47_24") (pintype "unspecified+no_connect"))
    )
    (net (code "89") (name "unconnected-(ESP32-IO48-Pad25)") (class "Default")
      (node (ref "ESP32") (pin "25") (pinfunction "IO48_25") (pintype "unspecified+no_connect"))
    )
    (net (code "90") (name "unconnected-(IRLEDREF-A-Pad1)") (class "Default")
      (node (ref "IRLEDREF") (pin "1") (pinfunction "A_1") (pintype "input+no_connect"))
    )
    (net (code "91") (name "unconnected-(IRRECREF-OUT-Pad1)") (class "Default")
      (node (ref "IRRECREF") (pin "1") (pinfunction "OUT_1") (pintype "unspecified+no_connect"))
    )
    (net (code "92") (name "unconnected-(IRRECREF-VS-Pad3)") (class "Default")
      (node (ref "IRRECREF") (pin "3") (pinfunction "VS_3") (pintype "unspecified+no_connect"))
    )
    (net (code "93") (name "unconnected-(MUX_I2C-SC6-Pad22)") (class "Default")
      (node (ref "MUX_I2C") (pin "22") (pinfunction "SC6_22") (pintype "unspecified+no_connect"))
    )
    (net (code "94") (name "unconnected-(MUX_I2C-SC7-Pad24)") (class "Default")
      (node (ref "MUX_I2C") (pin "24") (pinfunction "SC7_24") (pintype "unspecified+no_connect"))
    )
    (net (code "95") (name "unconnected-(MUX_I2C-SD6-Pad21)") (class "Default")
      (node (ref "MUX_I2C") (pin "21") (pinfunction "SD6_21") (pintype "unspecified+no_connect"))
    )
    (net (code "96") (name "unconnected-(MUX_I2C-SD7-Pad23)") (class "Default")
      (node (ref "MUX_I2C") (pin "23") (pinfunction "SD7_23") (pintype "unspecified+no_connect"))
    )
    (net (code "97") (name "unconnected-(MUX_RX-B7-Pad13)") (class "Default")
      (node (ref "MUX_RX") (pin "13") (pinfunction "B7_13") (pintype "unspecified+no_connect"))
    )
    (net (code "98") (name "unconnected-(MUX_RX-B8-Pad12)") (class "Default")
      (node (ref "MUX_RX") (pin "12") (pinfunction "B8_12") (pintype "unspecified+no_connect"))
    )
    (net (code "99") (name "unconnected-(MUX_RX-NC-Pad6)") (class "Default")
      (node (ref "MUX_RX") (pin "6") (pinfunction "NC_6") (pintype "unspecified+no_connect"))
    )
    (net (code "100") (name "unconnected-(MUX_TX-B7-Pad13)") (class "Default")
      (node (ref "MUX_TX") (pin "13") (pinfunction "B7_13") (pintype "unspecified+no_connect"))
    )
    (net (code "101") (name "unconnected-(MUX_TX-B8-Pad12)") (class "Default")
      (node (ref "MUX_TX") (pin "12") (pinfunction "B8_12") (pintype "unspecified+no_connect"))
    )
    (net (code "102") (name "unconnected-(MUX_TX-NC-Pad6)") (class "Default")
      (node (ref "MUX_TX") (pin "6") (pinfunction "NC_6") (pintype "unspecified+no_connect"))
    )
    (net (code "103") (name "unconnected-(RGB-DOUT-Pad3)") (class "Default")
      (node (ref "RGB") (pin "3") (pinfunction "DOUT_3") (pintype "unspecified+no_connect"))
    )
    (net (code "104") (name "unconnected-(RST_SW-Pad2)") (class "Default")
      (node (ref "RST_SW") (pin "2") (pinfunction "2_2") (pintype "unspecified+no_connect"))
    )
    (net (code "105") (name "unconnected-(RST_SW-Pad3)") (class "Default")
      (node (ref "RST_SW") (pin "3") (pinfunction "3_3") (pintype "unspecified+no_connect"))
    )
    (net (code "106") (name "unconnected-(TOF_REF-GND-Pad2)") (class "Default")
      (node (ref "TOF_REF") (pin "2") (pinfunction "GND_2") (pintype "unspecified+no_connect"))
    )
    (net (code "107") (name "unconnected-(TOF_REF-GPIO1-Pad5)") (class "Default")
      (node (ref "TOF_REF") (pin "5") (pinfunction "GPIO1_5") (pintype "unspecified+no_connect"))
    )
    (net (code "108") (name "unconnected-(TOF_REF-SCL-Pad3)") (class "Default")
      (node (ref "TOF_REF") (pin "3") (pinfunction "SCL_3") (pintype "unspecified+no_connect"))
    )
    (net (code "109") (name "unconnected-(TOF_REF-SDA-Pad4)") (class "Default")
      (node (ref "TOF_REF") (pin "4") (pinfunction "SDA_4") (pintype "unspecified+no_connect"))
    )
    (net (code "110") (name "unconnected-(TOF_REF-VIN-Pad1)") (class "Default")
      (node (ref "TOF_REF") (pin "1") (pinfunction "VIN_1") (pintype "unspecified+no_connect"))
    )
    (net (code "111") (name "unconnected-(TOF_REF-XSHUT-Pad6)") (class "Default")
      (node (ref "TOF_REF") (pin "6") (pinfunction "XSHUT_6") (pintype "unspecified+no_connect"))
    )
    (net (code "112") (name "unconnected-(U7-1A-Pad12)") (class "Default")
      (node (ref "U7") (pin "12") (pinfunction "1A_12") (pintype "unspecified+no_connect"))
    )
    (net (code "113") (name "unconnected-(U7-1B-Pad11)") (class "Default")
      (node (ref "U7") (pin "11") (pinfunction "1B_11") (pintype "unspecified+no_connect"))
    )
    (net (code "114") (name "unconnected-(U7-2A-Pad13)") (class "Default")
      (node (ref "U7") (pin "13") (pinfunction "2A_13") (pintype "unspecified+no_connect"))
    )
    (net (code "115") (name "unconnected-(U7-2B-Pad14)") (class "Default")
      (node (ref "U7") (pin "14") (pinfunction "2B_14") (pintype "unspecified+no_connect"))
    )
    (net (code "116") (name "unconnected-(U7-DIR-Pad8)") (class "Default")
      (node (ref "U7") (pin "8") (pinfunction "DIR_8") (pintype "unspecified+no_connect"))
    )
    (net (code "117") (name "unconnected-(U7-EN#-Pad1)") (class "Default")
      (node (ref "U7") (pin "1") (pinfunction "EN#_1") (pintype "unspecified+no_connect"))
    )
    (net (code "118") (name "unconnected-(U7-GND-Pad9)") (class "Default")
      (node (ref "U7") (pin "9") (pinfunction "GND_9") (pintype "unspecified+no_connect"))
    )
    (net (code "119") (name "unconnected-(U7-GND-Pad15)") (class "Default")
      (node (ref "U7") (pin "15") (pinfunction "GND_15") (pintype "unspecified+no_connect"))
    )
    (net (code "120") (name "unconnected-(U7-MS1-Pad2)") (class "Default")
      (node (ref "U7") (pin "2") (pinfunction "MS1_2") (pintype "unspecified+no_connect"))
    )
    (net (code "121") (name "unconnected-(U7-MS2-Pad3)") (class "Default")
      (node (ref "U7") (pin "3") (pinfunction "MS2_3") (pintype "unspecified+no_connect"))
    )
    (net (code "122") (name "unconnected-(U7-MS3-Pad4)") (class "Default")
      (node (ref "U7") (pin "4") (pinfunction "MS3_4") (pintype "unspecified+no_connect"))
    )
    (net (code "123") (name "unconnected-(U7-RST#-Pad5)") (class "Default")
      (node (ref "U7") (pin "5") (pinfunction "RST#_5") (pintype "unspecified+no_connect"))
    )
    (net (code "124") (name "unconnected-(U7-SLP#-Pad6)") (class "Default")
      (node (ref "U7") (pin "6") (pinfunction "SLP#_6") (pintype "unspecified+no_connect"))
    )
    (net (code "125") (name "unconnected-(U7-STEP-Pad7)") (class "Default")
      (node (ref "U7") (pin "7") (pinfunction "STEP_7") (pintype "unspecified+no_connect"))
    )
    (net (code "126") (name "unconnected-(U7-VDD-Pad10)") (class "Default")
      (node (ref "U7") (pin "10") (pinfunction "VDD_10") (pintype "unspecified+no_connect"))
    )
    (net (code "127") (name "unconnected-(U7-VMOT-Pad16)") (class "Default")
      (node (ref "U7") (pin "16") (pinfunction "VMOT_16") (pintype "unspecified+no_connect"))
    )
    (net (code "128") (name "unconnected-(USB-EP-Pad6)") (class "Default")
      (node (ref "USB") (pin "6") (pinfunction "EP_6") (pintype "unspecified+no_connect"))
    )
    (net (code "129") (name "unconnected-(USB-EP-Pad7)") (class "Default")
      (node (ref "USB") (pin "7") (pinfunction "EP_7") (pintype "unspecified+no_connect"))
    )
    (net (code "130") (name "unconnected-(USB-EP-Pad8)") (class "Default")
      (node (ref "USB") (pin "8") (pinfunction "EP_8") (pintype "unspecified+no_connect"))
    )
    (net (code "131") (name "unconnected-(USB-EP-Pad9)") (class "Default")
      (node (ref "USB") (pin "9") (pinfunction "EP_9") (pintype "unspecified+no_connect"))
    )
    (net (code "132") (name "unconnected-(USB-ID-Pad4)") (class "Default")
      (node (ref "USB") (pin "4") (pinfunction "ID_4") (pintype "unspecified+no_connect"))
    )
    (net (code "133") (name "unconnected-(USB2UART-CHR0-Pad15)") (class "Default")
      (node (ref "USB2UART") (pin "15") (pinfunction "CHR0_15") (pintype "unspecified+no_connect"))
    )
    (net (code "134") (name "unconnected-(USB2UART-CHR1-Pad14)") (class "Default")
      (node (ref "USB2UART") (pin "14") (pinfunction "CHR1_14") (pintype "unspecified+no_connect"))
    )
    (net (code "135") (name "unconnected-(USB2UART-CHREN-Pad13)") (class "Default")
      (node (ref "USB2UART") (pin "13") (pinfunction "CHREN_13") (pintype "unspecified+no_connect"))
    )
    (net (code "136") (name "unconnected-(USB2UART-CTS-Pad23)") (class "Default")
      (node (ref "USB2UART") (pin "23") (pinfunction "CTS_23") (pintype "unspecified+no_connect"))
    )
    (net (code "137") (name "unconnected-(USB2UART-DCD-Pad1)") (class "Default")
      (node (ref "USB2UART") (pin "1") (pinfunction "DCD_1") (pintype "unspecified+no_connect"))
    )
    (net (code "138") (name "unconnected-(USB2UART-DSR-Pad27)") (class "Default")
      (node (ref "USB2UART") (pin "27") (pinfunction "DSR_27") (pintype "unspecified+no_connect"))
    )
    (net (code "139") (name "unconnected-(USB2UART-DTR-Pad28)") (class "Default")
      (node (ref "USB2UART") (pin "28") (pinfunction "DTR_28") (pintype "unspecified+no_connect"))
    )
    (net (code "140") (name "unconnected-(USB2UART-GPIO.0{slash}TXT-Pad19)") (class "Default")
      (node (ref "USB2UART") (pin "19") (pinfunction "GPIO.0/TXT_19") (pintype "unspecified+no_connect"))
    )
    (net (code "141") (name "unconnected-(USB2UART-GPIO.1{slash}RXT-Pad18)") (class "Default")
      (node (ref "USB2UART") (pin "18") (pinfunction "GPIO.1/RXT_18") (pintype "unspecified+no_connect"))
    )
    (net (code "142") (name "unconnected-(USB2UART-GPIO.2{slash}RS485-Pad17)") (class "Default")
      (node (ref "USB2UART") (pin "17") (pinfunction "GPIO.2/RS485_17") (pintype "unspecified+no_connect"))
    )
    (net (code "143") (name "unconnected-(USB2UART-GPIO.3{slash}WAKEUP-Pad16)") (class "Default")
      (node (ref "USB2UART") (pin "16") (pinfunction "GPIO.3/WAKEUP_16") (pintype "unspecified+no_connect"))
    )
    (net (code "144") (name "unconnected-(USB2UART-GPIO.4-Pad22)") (class "Default")
      (node (ref "USB2UART") (pin "22") (pinfunction "GPIO.4_22") (pintype "unspecified+no_connect"))
    )
    (net (code "145") (name "unconnected-(USB2UART-GPIO.5-Pad21)") (class "Default")
      (node (ref "USB2UART") (pin "21") (pinfunction "GPIO.5_21") (pintype "unspecified+no_connect"))
    )
    (net (code "146") (name "unconnected-(USB2UART-GPIO.6-Pad20)") (class "Default")
      (node (ref "USB2UART") (pin "20") (pinfunction "GPIO.6_20") (pintype "unspecified+no_connect"))
    )
    (net (code "147") (name "unconnected-(USB2UART-NC-Pad10)") (class "Default")
      (node (ref "USB2UART") (pin "10") (pinfunction "NC_10") (pintype "unspecified+no_connect"))
    )
    (net (code "148") (name "unconnected-(USB2UART-RI{slash}CLK-Pad2)") (class "Default")
      (node (ref "USB2UART") (pin "2") (pinfunction "RI/CLK_2") (pintype "unspecified+no_connect"))
    )
    (net (code "149") (name "unconnected-(USB2UART-RTS-Pad24)") (class "Default")
      (node (ref "USB2UART") (pin "24") (pinfunction "RTS_24") (pintype "unspecified+no_connect"))
    )
    (net (code "150") (name "unconnected-(USB2UART-SUSPEND-Pad12)") (class "Default")
      (node (ref "USB2UART") (pin "12") (pinfunction "SUSPEND_12") (pintype "unspecified+no_connect"))
    )
    (net (code "151") (name "unconnected-(USB2UART-SUSPENDb-Pad11)") (class "Default")
      (node (ref "USB2UART") (pin "11") (pinfunction "SUSPENDb_11") (pintype "unspecified+no_connect"))
    )
  )
)
